# PDM-S12-V00-InputProtection.net
KiCad netlist of a schematic drawn in Altium Designer
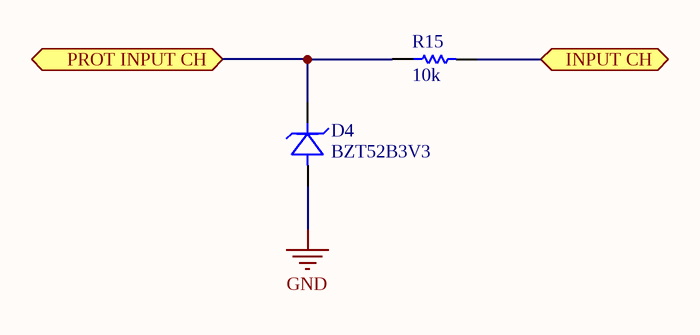
[diagram p0: PDM-S12-V00-InputProtection.SchDoc]

(export (version "E")
  (design (tool "Eeschema 10.0.6"))
  (components
    (comp (ref "D4")
      (value "BZT52B3V3")
      (footprint "SOD123")
      (description "Diode, SMD, Zener, 3.3V, 2%, 410mW, SOD-123")
      (libsource (lib "QUTMS_DiodeLibrary") (part "BZT52B3V3"))
    )
    (comp (ref "R15")
      (value "10k")
      (footprint "Res_ThinFilm_0603")
      (description "Resistor, SMD, 10k, 0.1W, 5%, 0603")
      (libsource (lib "StandardResistors") (part "10k 5% 0603"))
    )
  )
  (nets
    (net (code "1") (name "/INPUT CH") (class "Default")
      (node (ref "R15") (pin "2") (pinfunction "2_2") (pintype "passive"))
    )
    (net (code "2") (name "/PROT INPUT CH") (class "Default")
      (node (ref "D4") (pin "K") (pinfunction "Cathode_K") (pintype "passive"))
      (node (ref "R15") (pin "1") (pinfunction "1_1") (pintype "passive"))
    )
    (net (code "3") (name "GND") (class "Default")
      (node (ref "D4") (pin "A") (pinfunction "Anode_A") (pintype "passive"))
    )
  )
)
